# mod_sens.net
KiCad netlist of a schematic drawn in EAGLE
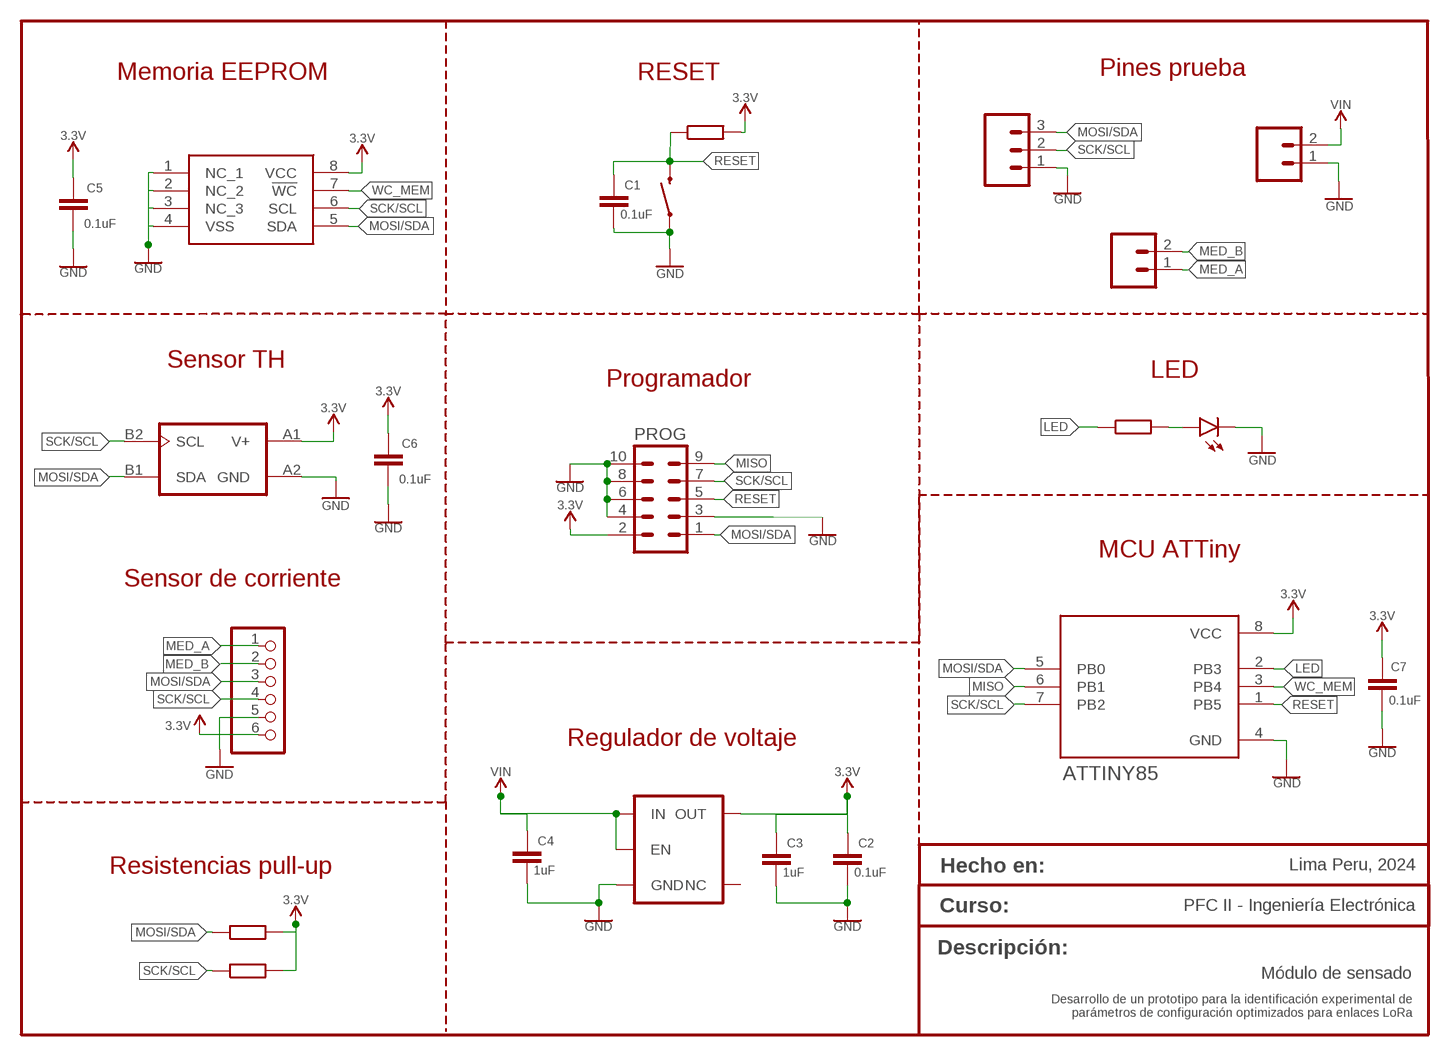
[diagram p0: schematic, sheet 1]

(export (version "E")
  (design (tool "Eeschema 10.0.6"))
  (components
    (comp (ref "ATTINY85")
      (value "ATTINY85")
      (footprint "eagle-import:SOIC127P798X216-8N")
      (fields (field (name "MF") "Microchip") (field (name "MP") "ATTINY85-20SU"))
      (libsource (lib "eagle-import") (part "ATTINY85-20SU"))
    )
    (comp (ref "C1")
      (value "0.1uF")
      (footprint "eagle-import:C0603K")
      (libsource (lib "eagle-import") (part "C-EUC0603K"))
    )
    (comp (ref "C2")
      (value "0.1uF")
      (footprint "eagle-import:C0603K")
      (libsource (lib "eagle-import") (part "C-EUC0603K"))
    )
    (comp (ref "C3")
      (value "1uF")
      (footprint "eagle-import:C0603K")
      (libsource (lib "eagle-import") (part "C-EUC0603K"))
    )
    (comp (ref "C4")
      (value "1uF")
      (footprint "eagle-import:C0603K")
      (libsource (lib "eagle-import") (part "C-EUC0603K"))
    )
    (comp (ref "C5")
      (value "0.1uF")
      (footprint "eagle-import:0603")
      (libsource (lib "eagle-import") (part "0.1UF-0603-25V-(+80/-20%)"))
    )
    (comp (ref "C6")
      (value "0.1uF")
      (footprint "eagle-import:0603")
      (libsource (lib "eagle-import") (part "0.1UF-0603-25V-(+80/-20%)"))
    )
    (comp (ref "C7")
      (value "0.1uF")
      (footprint "eagle-import:0603")
      (libsource (lib "eagle-import") (part "0.1UF-0603-25V-(+80/-20%)"))
    )
    (comp (ref "CURR")
      (value "curr")
      (footprint "eagle-import:1X02")
      (libsource (lib "eagle-import") (part "CONN_02"))
    )
    (comp (ref "CURR1")
      (value "curr")
      (footprint "eagle-import:1X02")
      (libsource (lib "eagle-import") (part "CONN_02"))
    )
    (comp (ref "I2C")
      (value "i2c")
      (footprint "eagle-import:1X03")
      (libsource (lib "eagle-import") (part "CONN_03"))
    )
    (comp (ref "L_ON")
      (value "LED_3MM")
      (footprint "eagle-import:LEDRD254W50D405H1055")
      (libsource (lib "eagle-import") (part "LED_3MM"))
    )
    (comp (ref "MEMORIA")
      (value "M24M01E")
      (footprint "eagle-import:SOIC127P600X175-8N")
      (fields
        (field (name "MANUFACTURER_PART_NUMBER") "M24M01E-FMN6TP")
        (field (name "MOUSER_PART_NUMBER") "511-M24M01E-FMN6TP")
      )
      (libsource (lib "eagle-import") (part "M24M01E-FMN6TP"))
    )
    (comp (ref "PROG")
      (value "ML10-3M")
      (footprint "eagle-import:3M_10")
      (libsource (lib "eagle-import") (part "ML10-3M"))
    )
    (comp (ref "R1")
      (value "68")
      (footprint "eagle-import:0207_10")
      (libsource (lib "eagle-import") (part "R-EU_0207/10"))
    )
    (comp (ref "R2")
      (value "1.5k")
      (footprint "eagle-import:0207_10")
      (libsource (lib "eagle-import") (part "R-EU_0207/10"))
    )
    (comp (ref "R3")
      (value "1.5k")
      (footprint "eagle-import:0207_10")
      (libsource (lib "eagle-import") (part "R-EU_0207/10"))
    )
    (comp (ref "R4")
      (value "10k")
      (footprint "eagle-import:0207_10")
      (libsource (lib "eagle-import") (part "R-EU_0207/10"))
    )
    (comp (ref "RESET")
      (value "MOMENTARY-SWITCH-SPST-PTH-6.0MM")
      (footprint "eagle-import:TACTILE_SWITCH_PTH_6.0MM")
      (libsource (lib "eagle-import") (part "MOMENTARY-SWITCH-SPST-PTH-6.0MM"))
    )
    (comp (ref "SENSOR_CURR")
      (value "sens_curr")
      (footprint "eagle-import:1X06")
      (libsource (lib "eagle-import") (part "PINHD-1X6"))
    )
    (comp (ref "SENSOR_TH")
      (value "TMP103GYFFR")
      (footprint "eagle-import:IC_TMP103DYFFR")
      (fields (field (name "MF") "Texas Instruments"))
      (libsource (lib "eagle-import") (part "TMP103GYFFR"))
    )
    (comp (ref "VOLT")
      (value "3.3V")
      (footprint "eagle-import:SOT23-5")
      (libsource (lib "eagle-import") (part "V_REG_AP2112K-3.3V"))
    )
  )
  (nets
    (net (code "1") (name "3.3V") (class "Default")
      (node (ref "ATTINY85") (pin "8") (pinfunction "VCC_8") (pintype "power_in"))
      (node (ref "C2") (pin "1") (pinfunction "1_1") (pintype "passive"))
      (node (ref "C3") (pin "1") (pinfunction "1_1") (pintype "passive"))
      (node (ref "C5") (pin "1") (pinfunction "1_1") (pintype "passive"))
      (node (ref "C6") (pin "1") (pinfunction "1_1") (pintype "passive"))
      (node (ref "C7") (pin "1") (pinfunction "1_1") (pintype "passive"))
      (node (ref "MEMORIA") (pin "8") (pinfunction "VCC_8") (pintype "bidirectional"))
      (node (ref "PROG") (pin "2") (pinfunction "2_2") (pintype "passive"))
      (node (ref "R2") (pin "2") (pinfunction "2_2") (pintype "passive"))
      (node (ref "R3") (pin "2") (pinfunction "2_2") (pintype "passive"))
      (node (ref "R4") (pin "2") (pinfunction "2_2") (pintype "passive"))
      (node (ref "SENSOR_CURR") (pin "6") (pinfunction "6_6") (pintype "passive"))
      (node (ref "SENSOR_TH") (pin "A1") (pinfunction "V+_A1") (pintype "power_in"))
      (node (ref "VOLT") (pin "5") (pinfunction "OUT_5") (pintype "passive"))
    )
    (net (code "2") (name "GND") (class "Default")
      (node (ref "ATTINY85") (pin "4") (pinfunction "GND_4") (pintype "power_in"))
      (node (ref "C1") (pin "2") (pinfunction "2_2") (pintype "passive"))
      (node (ref "C2") (pin "2") (pinfunction "2_2") (pintype "passive"))
      (node (ref "C3") (pin "2") (pinfunction "2_2") (pintype "passive"))
      (node (ref "C4") (pin "2") (pinfunction "2_2") (pintype "passive"))
      (node (ref "C5") (pin "2") (pinfunction "2_2") (pintype "passive"))
      (node (ref "C6") (pin "2") (pinfunction "2_2") (pintype "passive"))
      (node (ref "C7") (pin "2") (pinfunction "2_2") (pintype "passive"))
      (node (ref "CURR1") (pin "1") (pinfunction "1_1") (pintype "passive"))
      (node (ref "I2C") (pin "1") (pinfunction "1_1") (pintype "passive"))
      (node (ref "L_ON") (pin "C") (pinfunction "C_C") (pintype "passive"))
      (node (ref "MEMORIA") (pin "1") (pinfunction "NC_1_1") (pintype "bidirectional"))
      (node (ref "MEMORIA") (pin "2") (pinfunction "NC_2_2") (pintype "bidirectional"))
      (node (ref "MEMORIA") (pin "3") (pinfunction "NC_3_3") (pintype "bidirectional"))
      (node (ref "MEMORIA") (pin "4") (pinfunction "VSS_4") (pintype "bidirectional"))
      (node (ref "PROG") (pin "10") (pinfunction "10_10") (pintype "passive"))
      (node (ref "PROG") (pin "3") (pinfunction "3_3") (pintype "passive"))
      (node (ref "PROG") (pin "4") (pinfunction "4_4") (pintype "passive"))
      (node (ref "PROG") (pin "6") (pinfunction "6_6") (pintype "passive"))
      (node (ref "PROG") (pin "8") (pinfunction "8_8") (pintype "passive"))
      (node (ref "RESET") (pin "1") (pinfunction "1_1") (pintype "passive"))
      (node (ref "SENSOR_CURR") (pin "5") (pinfunction "5_5") (pintype "passive"))
      (node (ref "SENSOR_TH") (pin "A2") (pinfunction "GND_A2") (pintype "power_in"))
      (node (ref "VOLT") (pin "2") (pinfunction "GND_2") (pintype "input"))
    )
    (net (code "3") (name "LED") (class "Default")
      (node (ref "ATTINY85") (pin "2") (pinfunction "PB3_2") (pintype "bidirectional"))
      (node (ref "R1") (pin "1") (pinfunction "1_1") (pintype "passive"))
    )
    (net (code "4") (name "MED_A") (class "Default")
      (node (ref "CURR") (pin "1") (pinfunction "1_1") (pintype "passive"))
      (node (ref "SENSOR_CURR") (pin "1") (pinfunction "1_1") (pintype "passive"))
    )
    (net (code "5") (name "MED_B") (class "Default")
      (node (ref "CURR") (pin "2") (pinfunction "2_2") (pintype "passive"))
      (node (ref "SENSOR_CURR") (pin "2") (pinfunction "2_2") (pintype "passive"))
    )
    (net (code "6") (name "MISO") (class "Default")
      (node (ref "ATTINY85") (pin "6") (pinfunction "PB1_6") (pintype "bidirectional"))
      (node (ref "PROG") (pin "9") (pinfunction "9_9") (pintype "passive"))
    )
    (net (code "7") (name "MOSI{slash}SDA") (class "Default")
      (node (ref "ATTINY85") (pin "5") (pinfunction "PB0_5") (pintype "bidirectional"))
      (node (ref "I2C") (pin "3") (pinfunction "3_3") (pintype "passive"))
      (node (ref "MEMORIA") (pin "5") (pinfunction "SDA_5") (pintype "bidirectional"))
      (node (ref "PROG") (pin "1") (pinfunction "1_1") (pintype "passive"))
      (node (ref "R2") (pin "1") (pinfunction "1_1") (pintype "passive"))
      (node (ref "SENSOR_CURR") (pin "3") (pinfunction "3_3") (pintype "passive"))
      (node (ref "SENSOR_TH") (pin "B1") (pinfunction "SDA_B1") (pintype "bidirectional"))
    )
    (net (code "8") (name "Net-(L_ON-PadA)") (class "Default")
      (node (ref "L_ON") (pin "A") (pinfunction "A_A") (pintype "passive"))
      (node (ref "R1") (pin "2") (pinfunction "2_2") (pintype "passive"))
    )
    (net (code "9") (name "RESET") (class "Default")
      (node (ref "ATTINY85") (pin "1") (pinfunction "PB5_1") (pintype "bidirectional"))
      (node (ref "C1") (pin "1") (pinfunction "1_1") (pintype "passive"))
      (node (ref "PROG") (pin "5") (pinfunction "5_5") (pintype "passive"))
      (node (ref "R4") (pin "1") (pinfunction "1_1") (pintype "passive"))
      (node (ref "RESET") (pin "3") (pinfunction "2_3") (pintype "passive"))
    )
    (net (code "10") (name "SCK{slash}SCL") (class "Default")
      (node (ref "ATTINY85") (pin "7") (pinfunction "PB2_7") (pintype "bidirectional"))
      (node (ref "I2C") (pin "2") (pinfunction "2_2") (pintype "passive"))
      (node (ref "MEMORIA") (pin "6") (pinfunction "SCL_6") (pintype "bidirectional"))
      (node (ref "PROG") (pin "7") (pinfunction "7_7") (pintype "passive"))
      (node (ref "R3") (pin "1") (pinfunction "1_1") (pintype "passive"))
      (node (ref "SENSOR_CURR") (pin "4") (pinfunction "4_4") (pintype "passive"))
      (node (ref "SENSOR_TH") (pin "B2") (pinfunction "SCL_B2") (pintype "input"))
    )
    (net (code "11") (name "VIN") (class "Default")
      (node (ref "C4") (pin "1") (pinfunction "1_1") (pintype "passive"))
      (node (ref "CURR1") (pin "2") (pinfunction "2_2") (pintype "passive"))
      (node (ref "VOLT") (pin "1") (pinfunction "IN_1") (pintype "input"))
      (node (ref "VOLT") (pin "3") (pinfunction "EN_3") (pintype "input"))
    )
    (net (code "12") (name "WC_MEM") (class "Default")
      (node (ref "ATTINY85") (pin "3") (pinfunction "PB4_3") (pintype "bidirectional"))
      (node (ref "MEMORIA") (pin "7") (pinfunction "~{WC}_7") (pintype "bidirectional"))
    )
    (net (code "13") (name "unconnected-(VOLT-NC-Pad4)") (class "Default")
      (node (ref "VOLT") (pin "4") (pinfunction "NC_4") (pintype "no_connect"))
    )
  )
)
